# Schematic_for_report.net
KiCad netlist of a schematic drawn in EAGLE
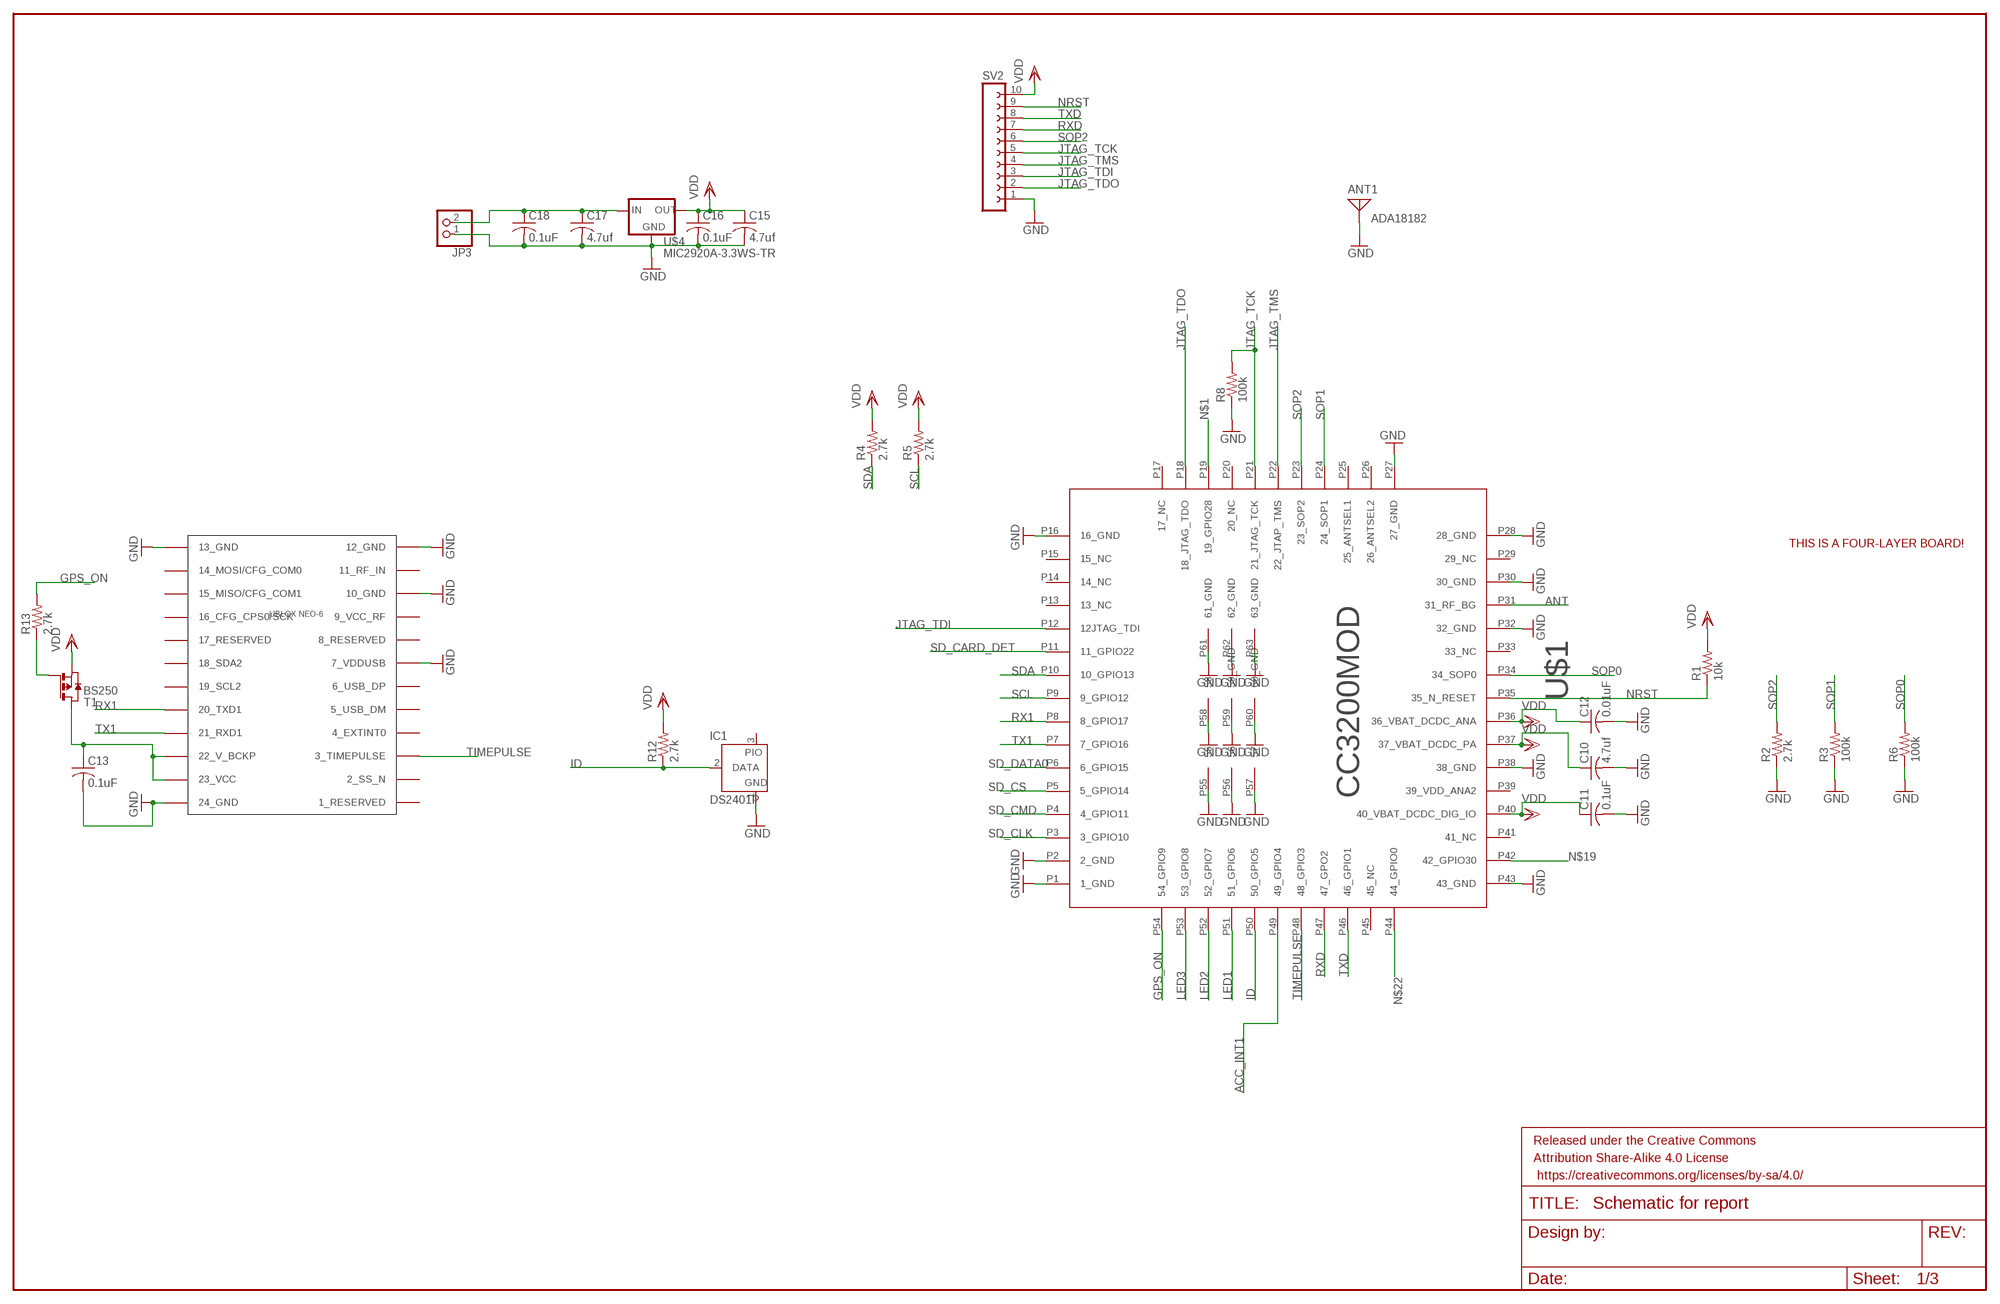
[diagram p0: schematic, sheet 1]
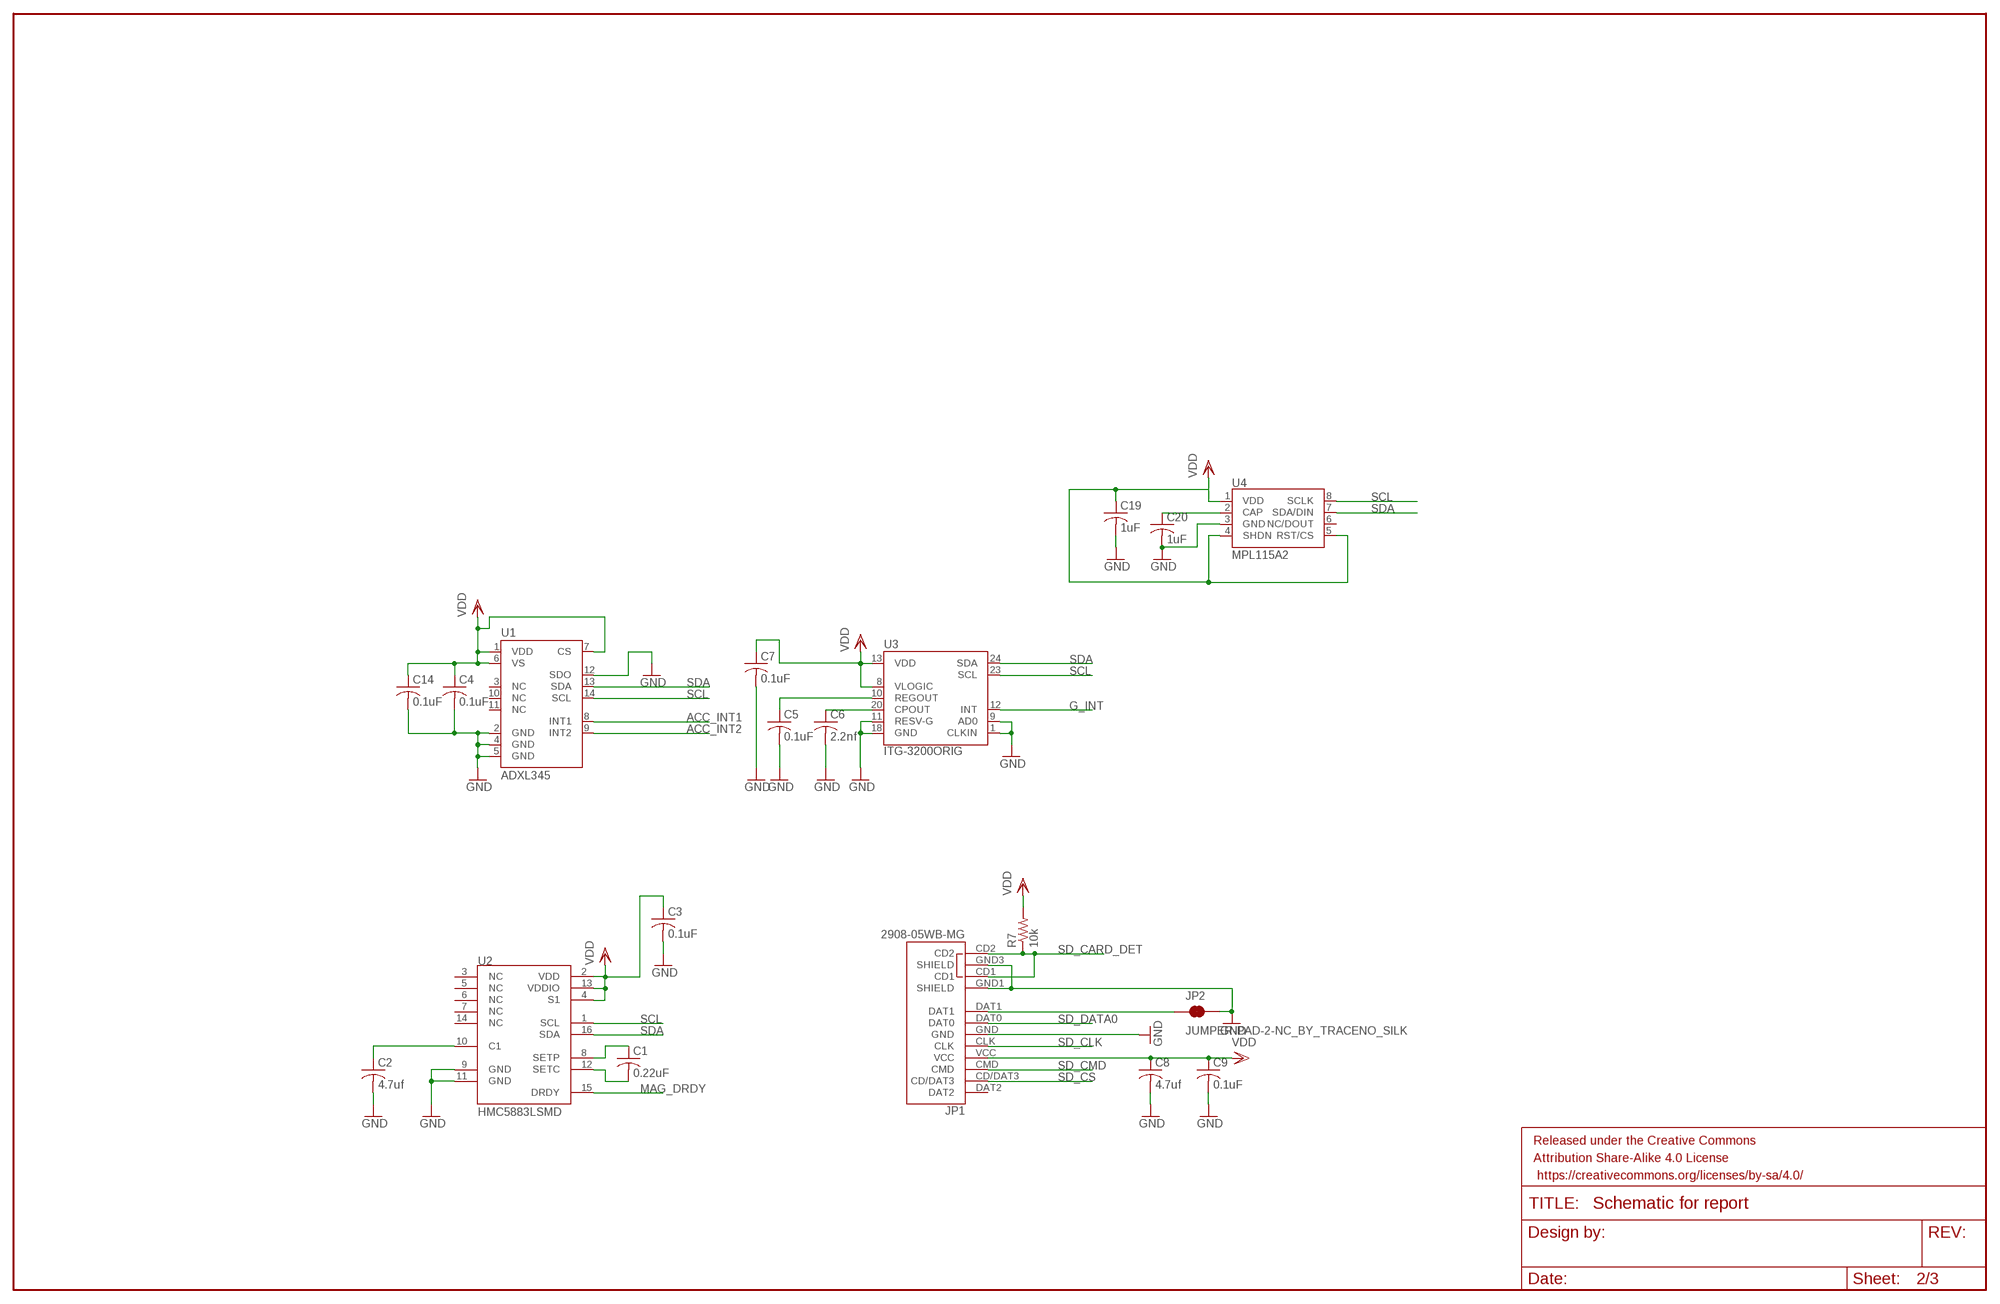
[diagram p1: schematic, sheet 2]
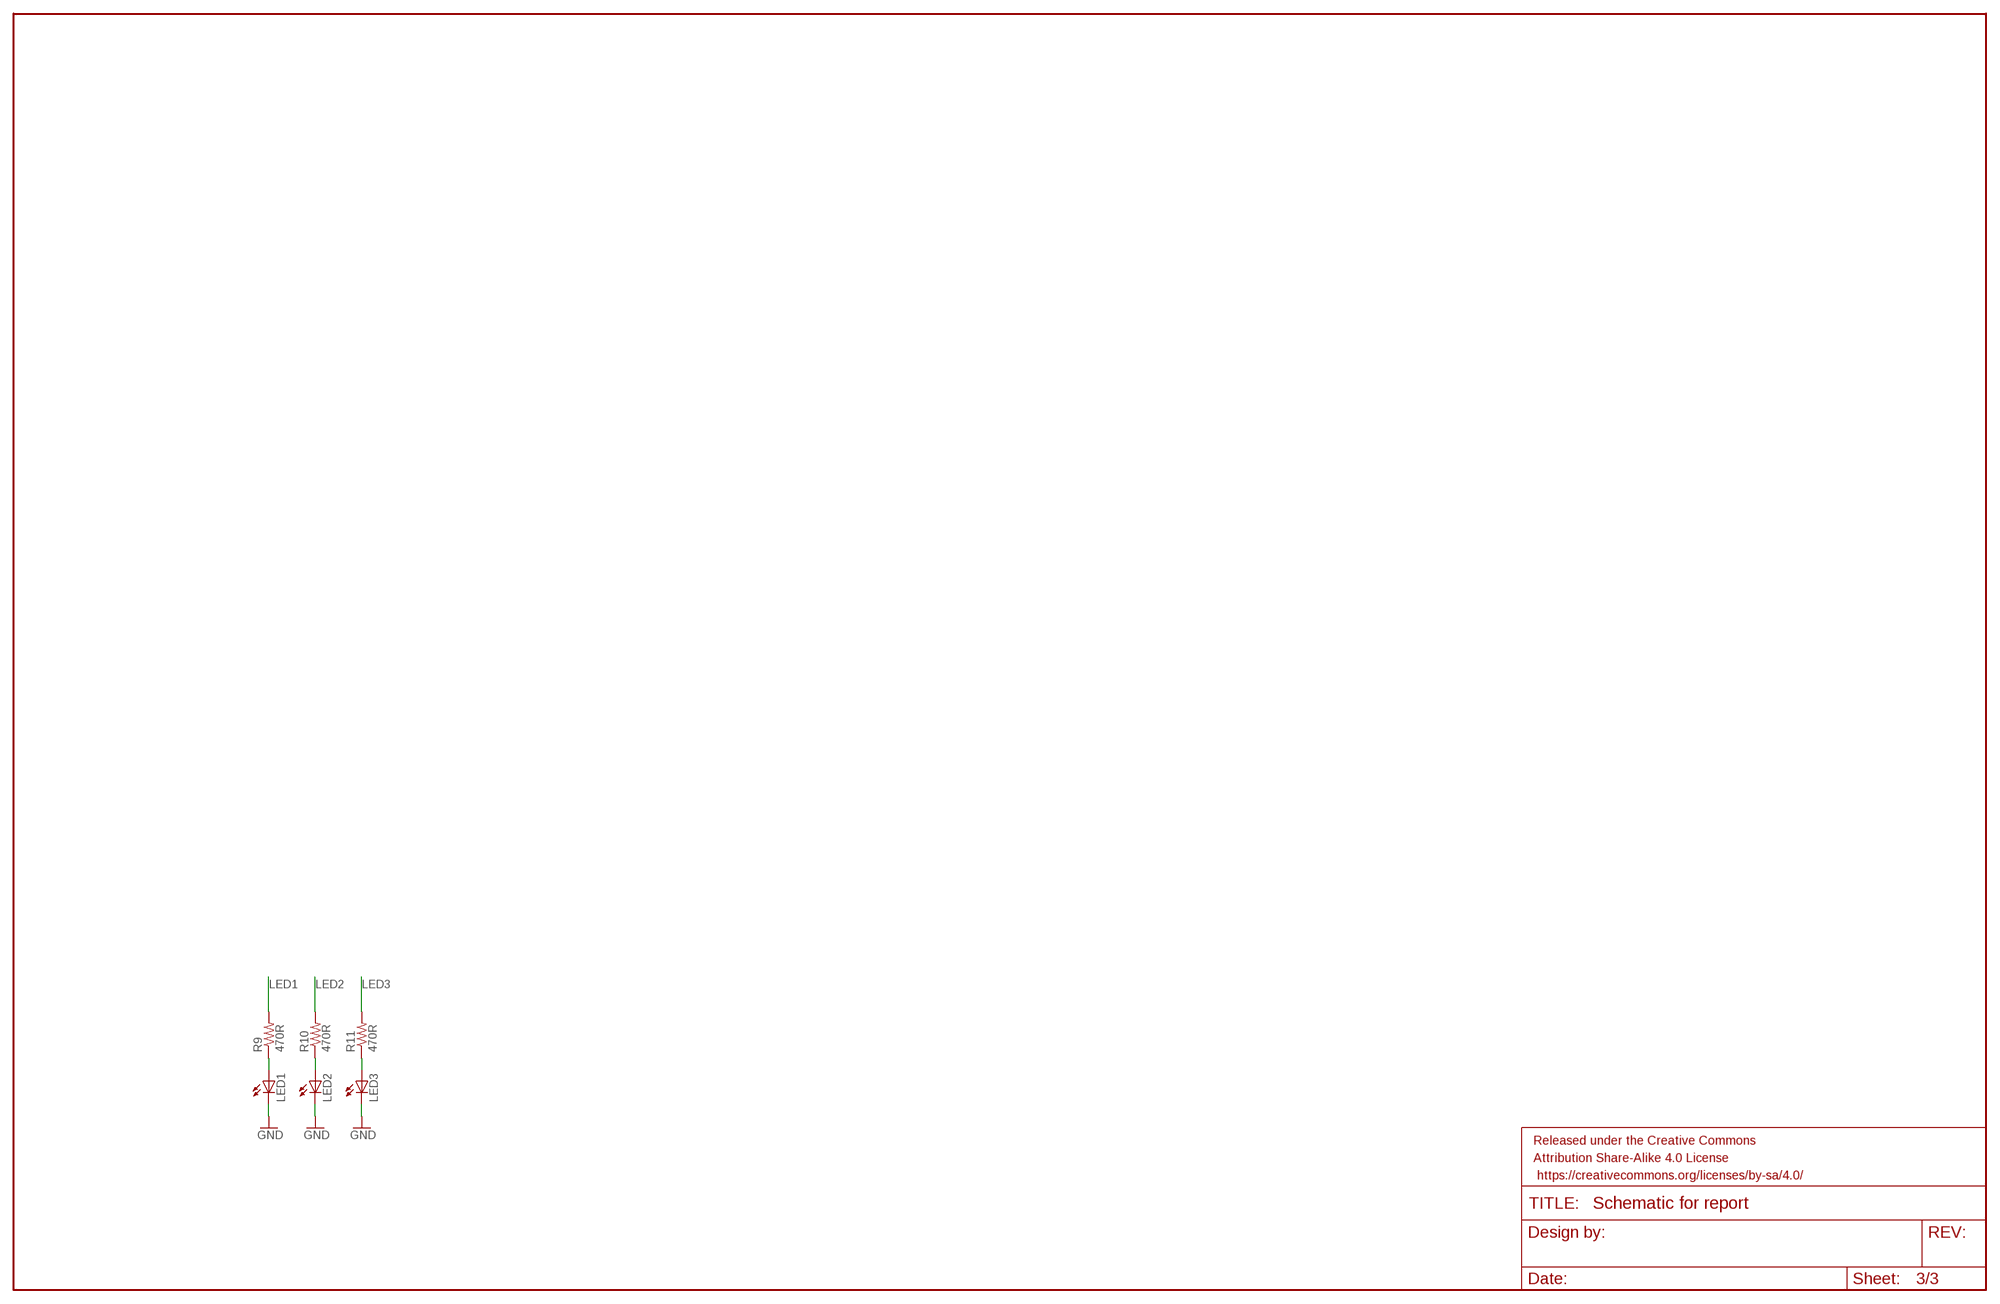
[diagram p2: schematic, sheet 3]

(export (version "E")
  (design (tool "Eeschema 10.0.6"))
  (components
    (comp (ref "FRAME3")
      (value "FRAME-LEDGER")
      (footprint "eagle-import:CREATIVE_COMMONS")
      (libsource (lib "eagle-import") (part "FRAME-LEDGER"))
    )
    (comp (ref "LED1")
      (value "LEDCHIPLED_0805")
      (footprint "eagle-import:CHIPLED_0805")
      (libsource (lib "eagle-import") (part "LEDCHIPLED_0805"))
    )
    (comp (ref "LED2")
      (value "LEDCHIPLED_0805")
      (footprint "eagle-import:CHIPLED_0805")
      (libsource (lib "eagle-import") (part "LEDCHIPLED_0805"))
    )
    (comp (ref "LED3")
      (value "LEDCHIPLED_0805")
      (footprint "eagle-import:CHIPLED_0805")
      (libsource (lib "eagle-import") (part "LEDCHIPLED_0805"))
    )
    (comp (ref "R9")
      (value "470R")
      (footprint "eagle-import:R0603")
      (libsource (lib "eagle-import") (part "R-US_R0603"))
    )
    (comp (ref "R10")
      (value "470R")
      (footprint "eagle-import:R0603")
      (libsource (lib "eagle-import") (part "R-US_R0603"))
    )
    (comp (ref "R11")
      (value "470R")
      (footprint "eagle-import:R0603")
      (libsource (lib "eagle-import") (part "R-US_R0603"))
    )
    (comp (ref "ANT1")
      (value "ADA18182")
      (footprint "eagle-import:PAD-01")
      (libsource (lib "eagle-import") (part "ANTENNA"))
    )
    (comp (ref "C10")
      (value "4.7uf")
      (footprint "eagle-import:C0805K")
      (libsource (lib "eagle-import") (part "C-USC0805K"))
    )
    (comp (ref "C11")
      (value "0.1uF")
      (footprint "eagle-import:C0805K")
      (libsource (lib "eagle-import") (part "C-USC0805K"))
    )
    (comp (ref "C12")
      (value "0.01uF")
      (footprint "eagle-import:C0805K")
      (libsource (lib "eagle-import") (part "C-USC0805K"))
    )
    (comp (ref "C13")
      (value "0.1uF")
      (footprint "eagle-import:C0805K")
      (libsource (lib "eagle-import") (part "C-USC0805K"))
    )
    (comp (ref "C15")
      (value "4.7uf")
      (footprint "eagle-import:C0805K")
      (libsource (lib "eagle-import") (part "C-USC0805K"))
    )
    (comp (ref "C16")
      (value "0.1uF")
      (footprint "eagle-import:C0805K")
      (libsource (lib "eagle-import") (part "C-USC0805K"))
    )
    (comp (ref "C17")
      (value "4.7uf")
      (footprint "eagle-import:C0805K")
      (libsource (lib "eagle-import") (part "C-USC0805K"))
    )
    (comp (ref "C18")
      (value "0.1uF")
      (footprint "eagle-import:C0805K")
      (libsource (lib "eagle-import") (part "C-USC0805K"))
    )
    (comp (ref "FRAME1")
      (value "FRAME-LEDGER")
      (footprint "eagle-import:CREATIVE_COMMONS")
      (libsource (lib "eagle-import") (part "FRAME-LEDGER"))
    )
    (comp (ref "IC1")
      (value "DS2401P")
      (footprint "eagle-import:TSOC6")
      (libsource (lib "eagle-import") (part "DS2405P"))
    )
    (comp (ref "JP3")
      (value "PINHD-1X2")
      (footprint "eagle-import:1X02")
      (libsource (lib "eagle-import") (part "PINHD-1X2"))
    )
    (comp (ref "R1")
      (value "10k")
      (footprint "eagle-import:R0603")
      (libsource (lib "eagle-import") (part "R-US_R0603"))
    )
    (comp (ref "R2")
      (value "2.7k")
      (footprint "eagle-import:R0603")
      (libsource (lib "eagle-import") (part "R-US_R0603"))
    )
    (comp (ref "R3")
      (value "100k")
      (footprint "eagle-import:R0603")
      (libsource (lib "eagle-import") (part "R-US_R0603"))
    )
    (comp (ref "R4")
      (value "2.7k")
      (footprint "eagle-import:R0603")
      (libsource (lib "eagle-import") (part "R-US_R0603"))
    )
    (comp (ref "R5")
      (value "2.7k")
      (footprint "eagle-import:R0603")
      (libsource (lib "eagle-import") (part "R-US_R0603"))
    )
    (comp (ref "R6")
      (value "100k")
      (footprint "eagle-import:R0603")
      (libsource (lib "eagle-import") (part "R-US_R0603"))
    )
    (comp (ref "R8")
      (value "100k")
      (footprint "eagle-import:R0603")
      (libsource (lib "eagle-import") (part "R-US_R0603"))
    )
    (comp (ref "R12")
      (value "2.7k")
      (footprint "eagle-import:R0603")
      (libsource (lib "eagle-import") (part "R-US_R0603"))
    )
    (comp (ref "R13")
      (value "2.7k")
      (footprint "eagle-import:R0603")
      (libsource (lib "eagle-import") (part "R-US_R0603"))
    )
    (comp (ref "SV2")
      (value "FE10-1")
      (footprint "eagle-import:FE10")
      (libsource (lib "eagle-import") (part "FE10-1"))
    )
    (comp (ref "T1")
      (value "BS250")
      (footprint "eagle-import:SOT-23")
      (libsource (lib "eagle-import") (part "PMOSSOT23"))
    )
    (comp (ref "U$1")
      (value "CC3200MOD")
      (footprint "eagle-import:CC3200MOD")
      (libsource (lib "eagle-import") (part "CC3200"))
    )
    (comp (ref "U$2")
      (value "UBLOX_NEO-7")
      (footprint "eagle-import:UBLOX_NEO-6P")
      (libsource (lib "eagle-import") (part "UBLOX_NEO-6"))
    )
    (comp (ref "U$3")
      (value "FOUR_LAYER_WARNING")
      (footprint "eagle-import:FOUR_LAYER_WARNING")
      (libsource (lib "eagle-import") (part "FOUR_LAYER_WARNING"))
    )
    (comp (ref "U$4")
      (value "MIC2920A-3.3WS-TR")
      (footprint "eagle-import:SOT223")
      (libsource (lib "eagle-import") (part "V_REG_MIC2920"))
    )
    (comp (ref "C1")
      (value "0.22uF")
      (footprint "eagle-import:C0805K")
      (libsource (lib "eagle-import") (part "C-USC0805K"))
    )
    (comp (ref "C2")
      (value "4.7uf")
      (footprint "eagle-import:C0805K")
      (libsource (lib "eagle-import") (part "C-USC0805K"))
    )
    (comp (ref "C3")
      (value "0.1uF")
      (footprint "eagle-import:C0805K")
      (libsource (lib "eagle-import") (part "C-USC0805K"))
    )
    (comp (ref "C4")
      (value "0.1uF")
      (footprint "eagle-import:C0805K")
      (libsource (lib "eagle-import") (part "C-USC0805K"))
    )
    (comp (ref "C5")
      (value "0.1uF")
      (footprint "eagle-import:C0805K")
      (libsource (lib "eagle-import") (part "C-USC0805K"))
    )
    (comp (ref "C6")
      (value "2.2nf")
      (footprint "eagle-import:C0805K")
      (libsource (lib "eagle-import") (part "C-USC0805K"))
    )
    (comp (ref "C7")
      (value "0.1uF")
      (footprint "eagle-import:C0805K")
      (libsource (lib "eagle-import") (part "C-USC0805K"))
    )
    (comp (ref "C8")
      (value "4.7uf")
      (footprint "eagle-import:C0805K")
      (libsource (lib "eagle-import") (part "C-USC0805K"))
    )
    (comp (ref "C9")
      (value "0.1uF")
      (footprint "eagle-import:C0805K")
      (libsource (lib "eagle-import") (part "C-USC0805K"))
    )
    (comp (ref "C14")
      (value "0.1uF")
      (footprint "eagle-import:C0805K")
      (libsource (lib "eagle-import") (part "C-USC0805K"))
    )
    (comp (ref "C19")
      (value "1uF")
      (footprint "eagle-import:C0805K")
      (libsource (lib "eagle-import") (part "C-USC0805K"))
    )
    (comp (ref "C20")
      (value "1uF")
      (footprint "eagle-import:C0805K")
      (libsource (lib "eagle-import") (part "C-USC0805K"))
    )
    (comp (ref "FRAME2")
      (value "FRAME-LEDGER")
      (footprint "eagle-import:CREATIVE_COMMONS")
      (libsource (lib "eagle-import") (part "FRAME-LEDGER"))
    )
    (comp (ref "JP1")
      (value "2908-05WB-MG")
      (footprint "eagle-import:MICRO-SD-SOCKET-SDIO")
      (libsource (lib "eagle-import") (part "USD-SDIO-SOCKET"))
    )
    (comp (ref "JP2")
      (value "JUMPER-PAD-2-NC_BY_TRACENO_SILK")
      (footprint "eagle-import:PAD-JUMPER-2-NC_BY_TRACE_NO_SILK")
      (libsource (lib "eagle-import") (part "JUMPER-PAD-2-NC_BY_TRACENO_SILK"))
    )
    (comp (ref "R7")
      (value "10k")
      (footprint "eagle-import:R0603")
      (libsource (lib "eagle-import") (part "R-US_R0603"))
    )
    (comp (ref "U1")
      (value "ADXL345")
      (footprint "eagle-import:LGA14")
      (libsource (lib "eagle-import") (part "ADXL345"))
    )
    (comp (ref "U2")
      (value "HMC5883LSMD")
      (footprint "eagle-import:16LPCC")
      (libsource (lib "eagle-import") (part "HMC5883LSMD"))
    )
    (comp (ref "U3")
      (value "ITG-3200ORIG")
      (footprint "eagle-import:QFN-24")
      (libsource (lib "eagle-import") (part "ITG-3200ORIG"))
    )
    (comp (ref "U4")
      (value "MPL115A2")
      (footprint "eagle-import:LGA8")
      (libsource (lib "eagle-import") (part "MPL115A"))
    )
  )
  (nets
    (net (code "1") (name "ACC_INT1") (class "Default")
      (node (ref "U$1") (pin "P49") (pinfunction "49_GPIO4_P49") (pintype "bidirectional"))
      (node (ref "U1") (pin "8") (pinfunction "INT1_8") (pintype "bidirectional"))
    )
    (net (code "2") (name "ACC_INT2") (class "Default")
      (node (ref "U1") (pin "9") (pinfunction "INT2_9") (pintype "bidirectional"))
    )
    (net (code "3") (name "ANT") (class "Default")
      (node (ref "U$1") (pin "P31") (pinfunction "31_RF_BG_P31") (pintype "bidirectional"))
    )
    (net (code "4") (name "GND") (class "Default")
      (node (ref "ANT1") (pin "1") (pinfunction "1_1") (pintype "output"))
      (node (ref "C10") (pin "2") (pinfunction "2_2") (pintype "passive"))
      (node (ref "C11") (pin "2") (pinfunction "2_2") (pintype "passive"))
      (node (ref "C12") (pin "2") (pinfunction "2_2") (pintype "passive"))
      (node (ref "C13") (pin "2") (pinfunction "2_2") (pintype "passive"))
      (node (ref "C14") (pin "2") (pinfunction "2_2") (pintype "passive"))
      (node (ref "C15") (pin "2") (pinfunction "2_2") (pintype "passive"))
      (node (ref "C16") (pin "2") (pinfunction "2_2") (pintype "passive"))
      (node (ref "C17") (pin "2") (pinfunction "2_2") (pintype "passive"))
      (node (ref "C18") (pin "2") (pinfunction "2_2") (pintype "passive"))
      (node (ref "C19") (pin "2") (pinfunction "2_2") (pintype "passive"))
      (node (ref "C2") (pin "2") (pinfunction "2_2") (pintype "passive"))
      (node (ref "C20") (pin "2") (pinfunction "2_2") (pintype "passive"))
      (node (ref "C3") (pin "2") (pinfunction "2_2") (pintype "passive"))
      (node (ref "C4") (pin "2") (pinfunction "2_2") (pintype "passive"))
      (node (ref "C5") (pin "2") (pinfunction "2_2") (pintype "passive"))
      (node (ref "C6") (pin "2") (pinfunction "2_2") (pintype "passive"))
      (node (ref "C7") (pin "2") (pinfunction "2_2") (pintype "passive"))
      (node (ref "C8") (pin "2") (pinfunction "2_2") (pintype "passive"))
      (node (ref "C9") (pin "2") (pinfunction "2_2") (pintype "passive"))
      (node (ref "IC1") (pin "1") (pinfunction "GND_1") (pintype "passive"))
      (node (ref "JP1") (pin "GND") (pinfunction "GND_GND") (pintype "bidirectional"))
      (node (ref "JP1") (pin "GND1") (pinfunction "SHIELD_GND1") (pintype "bidirectional"))
      (node (ref "JP1") (pin "GND3") (pinfunction "SHIELD_GND3") (pintype "bidirectional"))
      (node (ref "JP2") (pin "2") (pinfunction "2_2") (pintype "passive"))
      (node (ref "JP3") (pin "1") (pinfunction "1_1") (pintype "passive"))
      (node (ref "LED1") (pin "C") (pinfunction "C_C") (pintype "passive"))
      (node (ref "LED2") (pin "C") (pinfunction "C_C") (pintype "passive"))
      (node (ref "LED3") (pin "C") (pinfunction "C_C") (pintype "passive"))
      (node (ref "R2") (pin "1") (pinfunction "1_1") (pintype "passive"))
      (node (ref "R3") (pin "1") (pinfunction "1_1") (pintype "passive"))
      (node (ref "R6") (pin "1") (pinfunction "1_1") (pintype "passive"))
      (node (ref "R8") (pin "1") (pinfunction "1_1") (pintype "passive"))
      (node (ref "SV2") (pin "1") (pinfunction "1_1") (pintype "passive"))
      (node (ref "U$1") (pin "P1") (pinfunction "1_GND_P1") (pintype "bidirectional"))
      (node (ref "U$1") (pin "P16") (pinfunction "16_GND_P16") (pintype "bidirectional"))
      (node (ref "U$1") (pin "P2") (pinfunction "2_GND_P2") (pintype "bidirectional"))
      (node (ref "U$1") (pin "P27") (pinfunction "27_GND_P27") (pintype "bidirectional"))
      (node (ref "U$1") (pin "P28") (pinfunction "28_GND_P28") (pintype "bidirectional"))
      (node (ref "U$1") (pin "P30") (pinfunction "30_GND_P30") (pintype "bidirectional"))
      (node (ref "U$1") (pin "P32") (pinfunction "32_GND_P32") (pintype "bidirectional"))
      (node (ref "U$1") (pin "P38") (pinfunction "38_GND_P38") (pintype "bidirectional"))
      (node (ref "U$1") (pin "P43") (pinfunction "43_GND_P43") (pintype "bidirectional"))
      (node (ref "U$1") (pin "P55") (pinfunction "55_P55") (pintype "bidirectional"))
      (node (ref "U$1") (pin "P56") (pinfunction "56_P56") (pintype "bidirectional"))
      (node (ref "U$1") (pin "P57") (pinfunction "57_P57") (pintype "bidirectional"))
      (node (ref "U$1") (pin "P58") (pinfunction "58_P58") (pintype "bidirectional"))
      (node (ref "U$1") (pin "P59") (pinfunction "59_GND_P59") (pintype "bidirectional"))
      (node (ref "U$1") (pin "P60") (pinfunction "60_GND_P60") (pintype "bidirectional"))
      (node (ref "U$1") (pin "P61") (pinfunction "61_GND_P61") (pintype "bidirectional"))
      (node (ref "U$1") (pin "P62") (pinfunction "62_GND_P62") (pintype "bidirectional"))
      (node (ref "U$1") (pin "P63") (pinfunction "63_GND_P63") (pintype "bidirectional"))
      (node (ref "U$2") (pin "10_GND") (pinfunction "10_GND_10_GND") (pintype "bidirectional"))
      (node (ref "U$2") (pin "12_GND") (pinfunction "12_GND_12_GND") (pintype "bidirectional"))
      (node (ref "U$2") (pin "13_GND") (pinfunction "13_GND_13_GND") (pintype "bidirectional"))
      (node (ref "U$2") (pin "24_GND") (pinfunction "24_GND_24_GND") (pintype "bidirectional"))
      (node (ref "U$2") (pin "7_VDDUSB") (pinfunction "7_VDDUSB_7_VDDUSB") (pintype "bidirectional"))
      (node (ref "U$4") (pin "2") (pinfunction "GND_2") (pintype "input"))
      (node (ref "U1") (pin "12") (pinfunction "SDO_12") (pintype "bidirectional"))
      (node (ref "U1") (pin "2") (pinfunction "GND_2") (pintype "bidirectional"))
      (node (ref "U1") (pin "4") (pinfunction "GND_4") (pintype "bidirectional"))
      (node (ref "U1") (pin "5") (pinfunction "GND_5") (pintype "bidirectional"))
      (node (ref "U2") (pin "11") (pinfunction "GND_11") (pintype "bidirectional"))
      (node (ref "U2") (pin "9") (pinfunction "GND_9") (pintype "bidirectional"))
      (node (ref "U3") (pin "1") (pinfunction "CLKIN_1") (pintype "bidirectional"))
      (node (ref "U3") (pin "11") (pinfunction "RESV-G_11") (pintype "bidirectional"))
      (node (ref "U3") (pin "18") (pinfunction "GND_18") (pintype "bidirectional"))
      (node (ref "U3") (pin "9") (pinfunction "AD0_9") (pintype "bidirectional"))
      (node (ref "U4") (pin "3") (pinfunction "GND_3") (pintype "bidirectional"))
    )
    (net (code "5") (name "GPS_ON") (class "Default")
      (node (ref "R13") (pin "2") (pinfunction "2_2") (pintype "passive"))
      (node (ref "U$1") (pin "P54") (pinfunction "54_GPIO9_P54") (pintype "bidirectional"))
    )
    (net (code "6") (name "G_INT") (class "Default")
      (node (ref "U3") (pin "12") (pinfunction "INT_12") (pintype "bidirectional"))
    )
    (net (code "7") (name "ID") (class "Default")
      (node (ref "IC1") (pin "2") (pinfunction "DATA_2") (pintype "input"))
      (node (ref "R12") (pin "1") (pinfunction "1_1") (pintype "passive"))
      (node (ref "U$1") (pin "P50") (pinfunction "50_GPIO5_P50") (pintype "bidirectional"))
    )
    (net (code "8") (name "JTAG_TCK") (class "Default")
      (node (ref "R8") (pin "2") (pinfunction "2_2") (pintype "passive"))
      (node (ref "SV2") (pin "5") (pinfunction "5_5") (pintype "passive"))
      (node (ref "U$1") (pin "P21") (pinfunction "21_JTAG_TCK_P21") (pintype "bidirectional"))
    )
    (net (code "9") (name "JTAG_TDI") (class "Default")
      (node (ref "SV2") (pin "3") (pinfunction "3_3") (pintype "passive"))
      (node (ref "U$1") (pin "P12") (pinfunction "12JTAG_TDI_P12") (pintype "bidirectional"))
    )
    (net (code "10") (name "JTAG_TDO") (class "Default")
      (node (ref "SV2") (pin "2") (pinfunction "2_2") (pintype "passive"))
      (node (ref "U$1") (pin "P18") (pinfunction "18_JTAG_TDO_P18") (pintype "bidirectional"))
    )
    (net (code "11") (name "JTAG_TMS") (class "Default")
      (node (ref "SV2") (pin "4") (pinfunction "4_4") (pintype "passive"))
      (node (ref "U$1") (pin "P22") (pinfunction "22_JTAP_TMS_P22") (pintype "bidirectional"))
    )
    (net (code "12") (name "LED1") (class "Default")
      (node (ref "R9") (pin "2") (pinfunction "2_2") (pintype "passive"))
      (node (ref "U$1") (pin "P51") (pinfunction "51_GPIO6_P51") (pintype "bidirectional"))
    )
    (net (code "13") (name "LED2") (class "Default")
      (node (ref "R10") (pin "2") (pinfunction "2_2") (pintype "passive"))
      (node (ref "U$1") (pin "P52") (pinfunction "52_GPIO7_P52") (pintype "bidirectional"))
    )
    (net (code "14") (name "LED3") (class "Default")
      (node (ref "R11") (pin "2") (pinfunction "2_2") (pintype "passive"))
      (node (ref "U$1") (pin "P53") (pinfunction "53_GPIO8_P53") (pintype "bidirectional"))
    )
    (net (code "15") (name "MAG_DRDY") (class "Default")
      (node (ref "U2") (pin "15") (pinfunction "DRDY_15") (pintype "bidirectional"))
    )
    (net (code "16") (name "N$1") (class "Default")
      (node (ref "U$1") (pin "P19") (pinfunction "19_GPIO28_P19") (pintype "bidirectional"))
    )
    (net (code "17") (name "N$19") (class "Default")
      (node (ref "U$1") (pin "P42") (pinfunction "42_GPIO30_P42") (pintype "bidirectional"))
    )
    (net (code "18") (name "N$22") (class "Default")
      (node (ref "U$1") (pin "P44") (pinfunction "44_GPIO0_P44") (pintype "bidirectional"))
    )
    (net (code "19") (name "NRST") (class "Default")
      (node (ref "R1") (pin "1") (pinfunction "1_1") (pintype "passive"))
      (node (ref "SV2") (pin "9") (pinfunction "9_9") (pintype "passive"))
      (node (ref "U$1") (pin "P35") (pinfunction "35_N_RESET_P35") (pintype "bidirectional"))
    )
    (net (code "20") (name "Net-(JP1-PadDAT1)") (class "Default")
      (node (ref "JP1") (pin "DAT1") (pinfunction "DAT1_DAT1") (pintype "bidirectional"))
      (node (ref "JP2") (pin "1") (pinfunction "1_1") (pintype "passive"))
    )
    (net (code "21") (name "Net-(LED1-PadA)") (class "Default")
      (node (ref "LED1") (pin "A") (pinfunction "A_A") (pintype "passive"))
      (node (ref "R9") (pin "1") (pinfunction "1_1") (pintype "passive"))
    )
    (net (code "22") (name "Net-(LED2-PadA)") (class "Default")
      (node (ref "LED2") (pin "A") (pinfunction "A_A") (pintype "passive"))
      (node (ref "R10") (pin "1") (pinfunction "1_1") (pintype "passive"))
    )
    (net (code "23") (name "Net-(LED3-PadA)") (class "Default")
      (node (ref "LED3") (pin "A") (pinfunction "A_A") (pintype "passive"))
      (node (ref "R11") (pin "1") (pinfunction "1_1") (pintype "passive"))
    )
    (net (code "24") (name "Net-(T1-D)") (class "Default")
      (node (ref "C13") (pin "1") (pinfunction "1_1") (pintype "passive"))
      (node (ref "T1") (pin "1") (pinfunction "D_1") (pintype "passive"))
      (node (ref "U$2") (pin "22_V_BCKP") (pinfunction "22_V_BCKP_22_V_BCKP") (pintype "bidirectional"))
      (node (ref "U$2") (pin "23_VCC") (pinfunction "23_VCC_23_VCC") (pintype "bidirectional"))
    )
    (net (code "25") (name "Net-(T1-G)") (class "Default")
      (node (ref "R13") (pin "1") (pinfunction "1_1") (pintype "passive"))
      (node (ref "T1") (pin "3") (pinfunction "G_3") (pintype "passive"))
    )
    (net (code "26") (name "Net-(U$4-IN)") (class "Default")
      (node (ref "C17") (pin "1") (pinfunction "1_1") (pintype "passive"))
      (node (ref "C18") (pin "1") (pinfunction "1_1") (pintype "passive"))
      (node (ref "JP3") (pin "2") (pinfunction "2_2") (pintype "passive"))
      (node (ref "U$4") (pin "1") (pinfunction "IN_1") (pintype "input"))
    )
    (net (code "27") (name "Net-(U2-C1)") (class "Default")
      (node (ref "C2") (pin "1") (pinfunction "1_1") (pintype "passive"))
      (node (ref "U2") (pin "10") (pinfunction "C1_10") (pintype "bidirectional"))
    )
    (net (code "28") (name "Net-(U2-SETC)") (class "Default")
      (node (ref "C1") (pin "2") (pinfunction "2_2") (pintype "passive"))
      (node (ref "U2") (pin "12") (pinfunction "SETC_12") (pintype "bidirectional"))
    )
    (net (code "29") (name "Net-(U2-SETP)") (class "Default")
      (node (ref "C1") (pin "1") (pinfunction "1_1") (pintype "passive"))
      (node (ref "U2") (pin "8") (pinfunction "SETP_8") (pintype "bidirectional"))
    )
    (net (code "30") (name "Net-(U3-CPOUT)") (class "Default")
      (node (ref "C6") (pin "1") (pinfunction "1_1") (pintype "passive"))
      (node (ref "U3") (pin "20") (pinfunction "CPOUT_20") (pintype "bidirectional"))
    )
    (net (code "31") (name "Net-(U3-REGOUT)") (class "Default")
      (node (ref "C5") (pin "1") (pinfunction "1_1") (pintype "passive"))
      (node (ref "U3") (pin "10") (pinfunction "REGOUT_10") (pintype "bidirectional"))
    )
    (net (code "32") (name "Net-(U4-CAP)") (class "Default")
      (node (ref "C20") (pin "1") (pinfunction "1_1") (pintype "passive"))
      (node (ref "U4") (pin "2") (pinfunction "CAP_2") (pintype "bidirectional"))
    )
    (net (code "33") (name "RX1") (class "Default")
      (node (ref "U$1") (pin "P8") (pinfunction "8_GPIO17_P8") (pintype "bidirectional"))
      (node (ref "U$2") (pin "20_TXD1") (pinfunction "20_TXD1_20_TXD1") (pintype "bidirectional"))
    )
    (net (code "34") (name "RXD") (class "Default")
      (node (ref "SV2") (pin "7") (pinfunction "7_7") (pintype "passive"))
      (node (ref "U$1") (pin "P47") (pinfunction "47_GPO2_P47") (pintype "bidirectional"))
    )
    (net (code "35") (name "SCL") (class "Default")
      (node (ref "R5") (pin "1") (pinfunction "1_1") (pintype "passive"))
      (node (ref "U$1") (pin "P9") (pinfunction "9_GPIO12_P9") (pintype "bidirectional"))
      (node (ref "U1") (pin "14") (pinfunction "SCL_14") (pintype "bidirectional"))
      (node (ref "U2") (pin "1") (pinfunction "SCL_1") (pintype "bidirectional"))
      (node (ref "U3") (pin "23") (pinfunction "SCL_23") (pintype "bidirectional"))
      (node (ref "U4") (pin "8") (pinfunction "SCLK_8") (pintype "bidirectional"))
    )
    (net (code "36") (name "SDA") (class "Default")
      (node (ref "R4") (pin "1") (pinfunction "1_1") (pintype "passive"))
      (node (ref "U$1") (pin "P10") (pinfunction "10_GPIO13_P10") (pintype "bidirectional"))
      (node (ref "U1") (pin "13") (pinfunction "SDA_13") (pintype "bidirectional"))
      (node (ref "U2") (pin "16") (pinfunction "SDA_16") (pintype "bidirectional"))
      (node (ref "U3") (pin "24") (pinfunction "SDA_24") (pintype "bidirectional"))
      (node (ref "U4") (pin "7") (pinfunction "SDA/DIN_7") (pintype "bidirectional"))
    )
    (net (code "37") (name "SD_CARD_DET") (class "Default")
      (node (ref "JP1") (pin "CD1") (pinfunction "CD1_CD1") (pintype "bidirectional"))
      (node (ref "JP1") (pin "CD2") (pinfunction "CD2_CD2") (pintype "bidirectional"))
      (node (ref "R7") (pin "1") (pinfunction "1_1") (pintype "passive"))
      (node (ref "U$1") (pin "P11") (pinfunction "11_GPIO22_P11") (pintype "bidirectional"))
    )
    (net (code "38") (name "SD_CLK") (class "Default")
      (node (ref "JP1") (pin "CLK") (pinfunction "CLK_CLK") (pintype "bidirectional"))
      (node (ref "U$1") (pin "P3") (pinfunction "3_GPIO10_P3") (pintype "bidirectional"))
    )
    (net (code "39") (name "SD_CMD") (class "Default")
      (node (ref "JP1") (pin "CMD") (pinfunction "CMD_CMD") (pintype "bidirectional"))
      (node (ref "U$1") (pin "P4") (pinfunction "4_GPIO11_P4") (pintype "bidirectional"))
    )
    (net (code "40") (name "SD_CS") (class "Default")
      (node (ref "JP1") (pin "CD/DAT3") (pinfunction "CD/DAT3_CD/DAT3") (pintype "bidirectional"))
      (node (ref "U$1") (pin "P5") (pinfunction "5_GPIO14_P5") (pintype "bidirectional"))
    )
    (net (code "41") (name "SD_DATA0") (class "Default")
      (node (ref "JP1") (pin "DAT0") (pinfunction "DAT0_DAT0") (pintype "bidirectional"))
      (node (ref "U$1") (pin "P6") (pinfunction "6_GPIO15_P6") (pintype "bidirectional"))
    )
    (net (code "42") (name "SOP0") (class "Default")
      (node (ref "R6") (pin "2") (pinfunction "2_2") (pintype "passive"))
      (node (ref "U$1") (pin "P34") (pinfunction "34_SOP0_P34") (pintype "bidirectional"))
    )
    (net (code "43") (name "SOP1") (class "Default")
      (node (ref "R3") (pin "2") (pinfunction "2_2") (pintype "passive"))
      (node (ref "U$1") (pin "P24") (pinfunction "24_SOP1_P24") (pintype "bidirectional"))
    )
    (net (code "44") (name "SOP2") (class "Default")
      (node (ref "R2") (pin "2") (pinfunction "2_2") (pintype "passive"))
      (node (ref "SV2") (pin "6") (pinfunction "6_6") (pintype "passive"))
      (node (ref "U$1") (pin "P23") (pinfunction "23_SOP2_P23") (pintype "bidirectional"))
    )
    (net (code "45") (name "TIMEPULSE") (class "Default")
      (node (ref "U$1") (pin "P48") (pinfunction "48_GPIO3_P48") (pintype "bidirectional"))
      (node (ref "U$2") (pin "3_TIMEPULSE") (pinfunction "3_TIMEPULSE_3_TIMEPULSE") (pintype "bidirectional"))
    )
    (net (code "46") (name "TX1") (class "Default")
      (node (ref "U$1") (pin "P7") (pinfunction "7_GPIO16_P7") (pintype "bidirectional"))
      (node (ref "U$2") (pin "21_RXD1") (pinfunction "21_RXD1_21_RXD1") (pintype "bidirectional"))
    )
    (net (code "47") (name "TXD") (class "Default")
      (node (ref "SV2") (pin "8") (pinfunction "8_8") (pintype "passive"))
      (node (ref "U$1") (pin "P46") (pinfunction "46_GPIO1_P46") (pintype "bidirectional"))
    )
    (net (code "48") (name "VDD") (class "Default")
      (node (ref "C10") (pin "1") (pinfunction "1_1") (pintype "passive"))
      (node (ref "C11") (pin "1") (pinfunction "1_1") (pintype "passive"))
      (node (ref "C12") (pin "1") (pinfunction "1_1") (pintype "passive"))
      (node (ref "C14") (pin "1") (pinfunction "1_1") (pintype "passive"))
      (node (ref "C15") (pin "1") (pinfunction "1_1") (pintype "passive"))
      (node (ref "C16") (pin "1") (pinfunction "1_1") (pintype "passive"))
      (node (ref "C19") (pin "1") (pinfunction "1_1") (pintype "passive"))
      (node (ref "C3") (pin "1") (pinfunction "1_1") (pintype "passive"))
      (node (ref "C4") (pin "1") (pinfunction "1_1") (pintype "passive"))
      (node (ref "C7") (pin "1") (pinfunction "1_1") (pintype "passive"))
      (node (ref "C8") (pin "1") (pinfunction "1_1") (pintype "passive"))
      (node (ref "C9") (pin "1") (pinfunction "1_1") (pintype "passive"))
      (node (ref "JP1") (pin "VCC") (pinfunction "VCC_VCC") (pintype "bidirectional"))
      (node (ref "R1") (pin "2") (pinfunction "2_2") (pintype "passive"))
      (node (ref "R12") (pin "2") (pinfunction "2_2") (pintype "passive"))
      (node (ref "R4") (pin "2") (pinfunction "2_2") (pintype "passive"))
      (node (ref "R5") (pin "2") (pinfunction "2_2") (pintype "passive"))
      (node (ref "R7") (pin "2") (pinfunction "2_2") (pintype "passive"))
      (node (ref "SV2") (pin "10") (pinfunction "10_10") (pintype "passive"))
      (node (ref "T1") (pin "2") (pinfunction "S_2") (pintype "passive"))
      (node (ref "U$1") (pin "P36") (pinfunction "36_VBAT_DCDC_ANA_P36") (pintype "bidirectional"))
      (node (ref "U$1") (pin "P37") (pinfunction "37_VBAT_DCDC_PA_P37") (pintype "bidirectional"))
      (node (ref "U$1") (pin "P40") (pinfunction "40_VBAT_DCDC_DIG_IO_P40") (pintype "bidirectional"))
      (node (ref "U$4") (pin "3") (pinfunction "OUT_3") (pintype "passive"))
      (node (ref "U1") (pin "1") (pinfunction "VDD_1") (pintype "bidirectional"))
      (node (ref "U1") (pin "6") (pinfunction "VS_6") (pintype "bidirectional"))
      (node (ref "U1") (pin "7") (pinfunction "CS_7") (pintype "bidirectional"))
      (node (ref "U2") (pin "13") (pinfunction "VDDIO_13") (pintype "bidirectional"))
      (node (ref "U2") (pin "2") (pinfunction "VDD_2") (pintype "bidirectional"))
      (node (ref "U2") (pin "4") (pinfunction "S1_4") (pintype "bidirectional"))
      (node (ref "U3") (pin "13") (pinfunction "VDD_13") (pintype "bidirectional"))
      (node (ref "U3") (pin "8") (pinfunction "VLOGIC_8") (pintype "bidirectional"))
      (node (ref "U4") (pin "1") (pinfunction "VDD_1") (pintype "bidirectional"))
      (node (ref "U4") (pin "4") (pinfunction "SHDN_4") (pintype "bidirectional"))
      (node (ref "U4") (pin "5") (pinfunction "RST/CS_5") (pintype "bidirectional"))
    )
    (net (code "49") (name "unconnected-(IC1-PIO-Pad3)") (class "Default")
      (node (ref "IC1") (pin "3") (pinfunction "PIO_3") (pintype "passive"))
    )
    (net (code "50") (name "unconnected-(JP1-PadDAT2)") (class "Default")
      (node (ref "JP1") (pin "DAT2") (pinfunction "DAT2_DAT2") (pintype "bidirectional"))
    )
    (net (code "51") (name "unconnected-(U$1-13_NC-PadP13)") (class "Default")
      (node (ref "U$1") (pin "P13") (pinfunction "13_NC_P13") (pintype "bidirectional"))
    )
    (net (code "52") (name "unconnected-(U$1-14_NC-PadP14)") (class "Default")
      (node (ref "U$1") (pin "P14") (pinfunction "14_NC_P14") (pintype "bidirectional"))
    )
    (net (code "53") (name "unconnected-(U$1-15_NC-PadP15)") (class "Default")
      (node (ref "U$1") (pin "P15") (pinfunction "15_NC_P15") (pintype "bidirectional"))
    )
    (net (code "54") (name "unconnected-(U$1-17_NC-PadP17)") (class "Default")
      (node (ref "U$1") (pin "P17") (pinfunction "17_NC_P17") (pintype "bidirectional"))
    )
    (net (code "55") (name "unconnected-(U$1-20_NC-PadP20)") (class "Default")
      (node (ref "U$1") (pin "P20") (pinfunction "20_NC_P20") (pintype "bidirectional"))
    )
    (net (code "56") (name "unconnected-(U$1-25_ANTSEL1-PadP25)") (class "Default")
      (node (ref "U$1") (pin "P25") (pinfunction "25_ANTSEL1_P25") (pintype "bidirectional"))
    )
    (net (code "57") (name "unconnected-(U$1-26_ANTSEL2-PadP26)") (class "Default")
      (node (ref "U$1") (pin "P26") (pinfunction "26_ANTSEL2_P26") (pintype "bidirectional"))
    )
    (net (code "58") (name "unconnected-(U$1-29_NC-PadP29)") (class "Default")
      (node (ref "U$1") (pin "P29") (pinfunction "29_NC_P29") (pintype "bidirectional"))
    )
    (net (code "59") (name "unconnected-(U$1-33_NC-PadP33)") (class "Default")
      (node (ref "U$1") (pin "P33") (pinfunction "33_NC_P33") (pintype "bidirectional"))
    )
    (net (code "60") (name "unconnected-(U$1-39_VDD_ANA2-PadP39)") (class "Default")
      (node (ref "U$1") (pin "P39") (pinfunction "39_VDD_ANA2_P39") (pintype "bidirectional"))
    )
    (net (code "61") (name "unconnected-(U$1-41_NC-PadP41)") (class "Default")
      (node (ref "U$1") (pin "P41") (pinfunction "41_NC_P41") (pintype "bidirectional"))
    )
    (net (code "62") (name "unconnected-(U$1-45_NC-PadP45)") (class "Default")
      (node (ref "U$1") (pin "P45") (pinfunction "45_NC_P45") (pintype "bidirectional"))
    )
    (net (code "63") (name "unconnected-(U$2-Pad1_RESERVED)") (class "Default")
      (node (ref "U$2") (pin "1_RESERVED") (pinfunction "1_RESERVED_1_RESERVED") (pintype "bidirectional"))
    )
    (net (code "64") (name "unconnected-(U$2-Pad2_SS_N)") (class "Default")
      (node (ref "U$2") (pin "2_SS_N") (pinfunction "2_SS_N_2_SS_N") (pintype "bidirectional"))
    )
    (net (code "65") (name "unconnected-(U$2-Pad4_EXTINT0)") (class "Default")
      (node (ref "U$2") (pin "4_EXTINT0") (pinfunction "4_EXTINT0_4_EXTINT0") (pintype "bidirectional"))
    )
    (net (code "66") (name "unconnected-(U$2-Pad5_USB_DM)") (class "Default")
      (node (ref "U$2") (pin "5_USB_DM") (pinfunction "5_USB_DM_5_USB_DM") (pintype "bidirectional"))
    )
    (net (code "67") (name "unconnected-(U$2-Pad6_USB_DP)") (class "Default")
      (node (ref "U$2") (pin "6_USB_DP") (pinfunction "6_USB_DP_6_USB_DP") (pintype "bidirectional"))
    )
    (net (code "68") (name "unconnected-(U$2-Pad8_RESERVED)") (class "Default")
      (node (ref "U$2") (pin "8_RESERVED") (pinfunction "8_RESERVED_8_RESERVED") (pintype "bidirectional"))
    )
    (net (code "69") (name "unconnected-(U$2-Pad9_VCC_RF)") (class "Default")
      (node (ref "U$2") (pin "9_VCC_RF") (pinfunction "9_VCC_RF_9_VCC_RF") (pintype "bidirectional"))
    )
    (net (code "70") (name "unconnected-(U$2-Pad11_RF_IN)") (class "Default")
      (node (ref "U$2") (pin "11_RF_IN") (pinfunction "11_RF_IN_11_RF_IN") (pintype "bidirectional"))
    )
    (net (code "71") (name "unconnected-(U$2-Pad14_MOSI{slash}CFG_COM0)") (class "Default")
      (node (ref "U$2") (pin "14_MOSI/CFG_COM0") (pinfunction "14_MOSI/CFG_COM0_14_MOSI/CFG_COM0") (pintype "bidirectional"))
    )
    (net (code "72") (name "unconnected-(U$2-Pad15_MISO{slash}CFG_COM1)") (class "Default")
      (node (ref "U$2") (pin "15_MISO/CFG_COM1") (pinfunction "15_MISO/CFG_COM1_15_MISO/CFG_COM1") (pintype "bidirectional"))
    )
    (net (code "73") (name "unconnected-(U$2-Pad16_CFG_CPS0{slash}SCK)") (class "Default")
      (node (ref "U$2") (pin "16_CFG_CPS0/SCK") (pinfunction "16_CFG_CPS0/SCK_16_CFG_CPS0/SCK") (pintype "bidirectional"))
    )
    (net (code "74") (name "unconnected-(U$2-Pad17_RESERVED)") (class "Default")
      (node (ref "U$2") (pin "17_RESERVED") (pinfunction "17_RESERVED_17_RESERVED") (pintype "bidirectional"))
    )
    (net (code "75") (name "unconnected-(U$2-Pad18_SDA2)") (class "Default")
      (node (ref "U$2") (pin "18_SDA2") (pinfunction "18_SDA2_18_SDA2") (pintype "bidirectional"))
    )
    (net (code "76") (name "unconnected-(U$2-Pad19_SCL2)") (class "Default")
      (node (ref "U$2") (pin "19_SCL2") (pinfunction "19_SCL2_19_SCL2") (pintype "bidirectional"))
    )
    (net (code "77") (name "unconnected-(U1-NC-Pad3)") (class "Default")
      (node (ref "U1") (pin "3") (pinfunction "NC_3") (pintype "bidirectional"))
    )
    (net (code "78") (name "unconnected-(U1-NC-Pad10)") (class "Default")
      (node (ref "U1") (pin "10") (pinfunction "NC_10") (pintype "bidirectional"))
    )
    (net (code "79") (name "unconnected-(U1-NC-Pad11)") (class "Default")
      (node (ref "U1") (pin "11") (pinfunction "NC_11") (pintype "bidirectional"))
    )
    (net (code "80") (name "unconnected-(U2-NC-Pad3)") (class "Default")
      (node (ref "U2") (pin "3") (pinfunction "NC_3") (pintype "bidirectional"))
    )
    (net (code "81") (name "unconnected-(U2-NC-Pad5)") (class "Default")
      (node (ref "U2") (pin "5") (pinfunction "NC_5") (pintype "bidirectional"))
    )
    (net (code "82") (name "unconnected-(U2-NC-Pad6)") (class "Default")
      (node (ref "U2") (pin "6") (pinfunction "NC_6") (pintype "bidirectional"))
    )
    (net (code "83") (name "unconnected-(U2-NC-Pad7)") (class "Default")
      (node (ref "U2") (pin "7") (pinfunction "NC_7") (pintype "bidirectional"))
    )
    (net (code "84") (name "unconnected-(U2-NC-Pad14)") (class "Default")
      (node (ref "U2") (pin "14") (pinfunction "NC_14") (pintype "bidirectional"))
    )
    (net (code "85") (name "unconnected-(U4-NC{slash}DOUT-Pad6)") (class "Default")
      (node (ref "U4") (pin "6") (pinfunction "NC/DOUT_6") (pintype "bidirectional"))
    )
  )
)
